# balise_mettrice.net
KiCad netlist of a schematic drawn in EAGLE
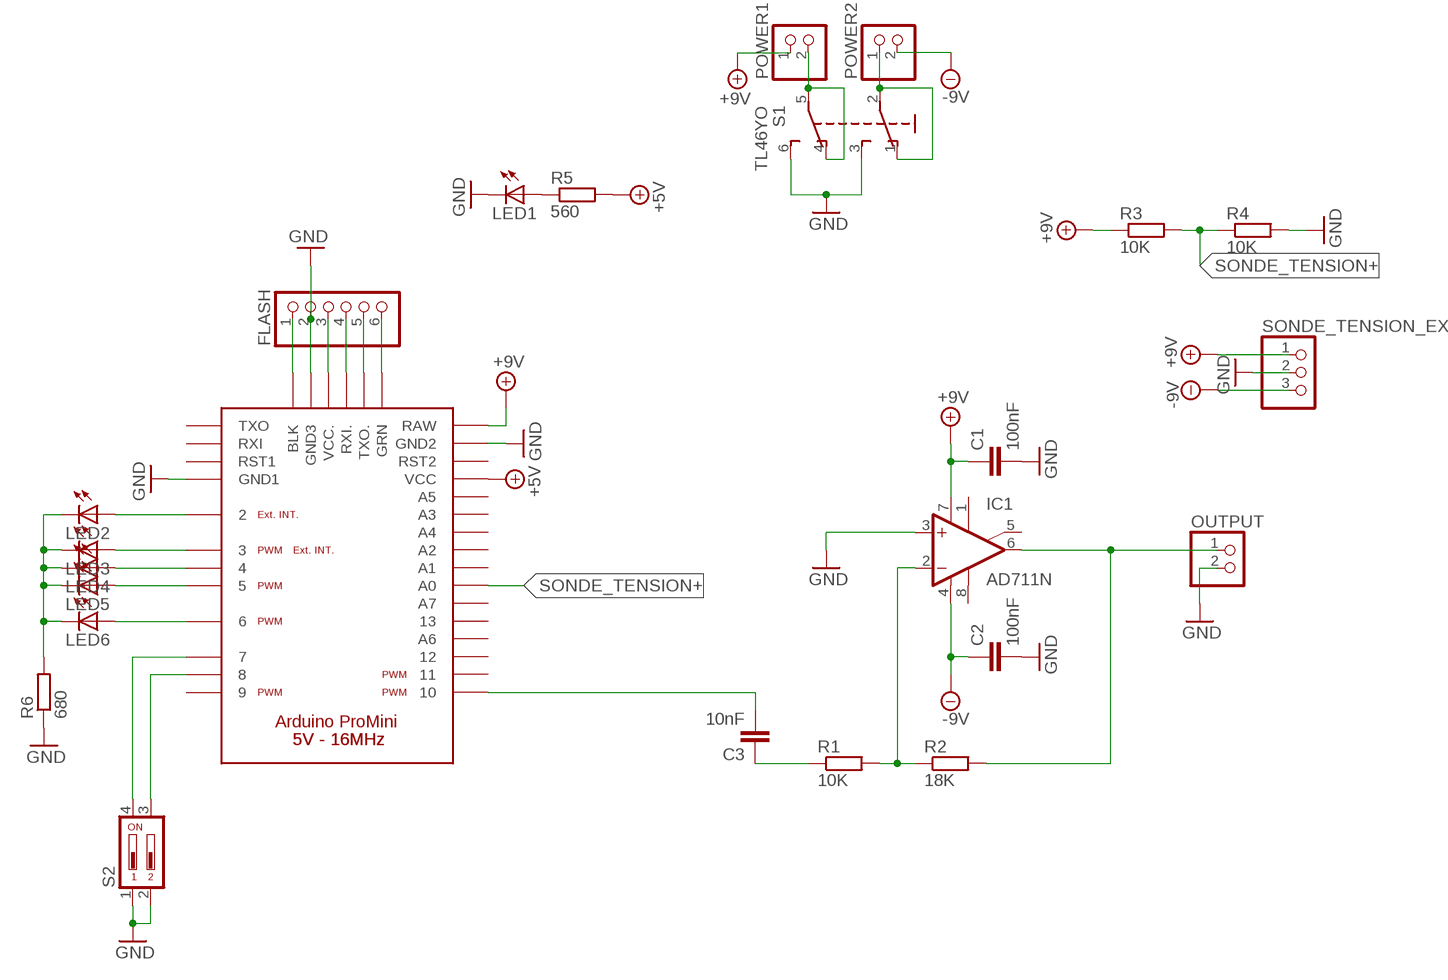
[diagram p0: schematic, sheet 1]

(export (version "E")
  (design (tool "Eeschema 10.0.6"))
  (components
    (comp (ref "C1")
      (value "100nF")
      (footprint "eagle-import:C050-024X044")
      (libsource (lib "eagle-import") (part "C-EU050-024X044"))
    )
    (comp (ref "C2")
      (value "100nF")
      (footprint "eagle-import:C050-024X044")
      (libsource (lib "eagle-import") (part "C-EU050-024X044"))
    )
    (comp (ref "C3")
      (value "10nF")
      (footprint "eagle-import:C050-024X044")
      (libsource (lib "eagle-import") (part "C-EU050-024X044"))
    )
    (comp (ref "FLASH")
      (value "PINHD-1X6/90")
      (footprint "eagle-import:1X06_90")
      (libsource (lib "eagle-import") (part "PINHD-1X6/90"))
    )
    (comp (ref "IC1")
      (value "AD711N")
      (footprint "eagle-import:DIL08")
      (libsource (lib "eagle-import") (part "AD711N"))
    )
    (comp (ref "LED1")
      (value "LEDB155")
      (footprint "eagle-import:Q62902-B155")
      (libsource (lib "eagle-import") (part "LEDB155"))
    )
    (comp (ref "LED2")
      (value "LED3MM")
      (footprint "eagle-import:LED3MM")
      (libsource (lib "eagle-import") (part "LED3MM"))
    )
    (comp (ref "LED3")
      (value "LED3MM")
      (footprint "eagle-import:LED3MM")
      (libsource (lib "eagle-import") (part "LED3MM"))
    )
    (comp (ref "LED4")
      (value "LED3MM")
      (footprint "eagle-import:LED3MM")
      (libsource (lib "eagle-import") (part "LED3MM"))
    )
    (comp (ref "LED5")
      (value "LED3MM")
      (footprint "eagle-import:LED3MM")
      (libsource (lib "eagle-import") (part "LED3MM"))
    )
    (comp (ref "LED6")
      (value "LED3MM")
      (footprint "eagle-import:LED3MM")
      (libsource (lib "eagle-import") (part "LED3MM"))
    )
    (comp (ref "OUTPUT")
      (value "PINHD-1X2")
      (footprint "eagle-import:1X02")
      (libsource (lib "eagle-import") (part "PINHD-1X2"))
    )
    (comp (ref "POWER1")
      (value "PINHD-1X2")
      (footprint "eagle-import:1X02")
      (libsource (lib "eagle-import") (part "PINHD-1X2"))
    )
    (comp (ref "POWER2")
      (value "PINHD-1X2")
      (footprint "eagle-import:1X02")
      (libsource (lib "eagle-import") (part "PINHD-1X2"))
    )
    (comp (ref "R1")
      (value "10K")
      (footprint "eagle-import:0204_7")
      (libsource (lib "eagle-import") (part "R-EU_0204/7"))
    )
    (comp (ref "R2")
      (value "18K")
      (footprint "eagle-import:0204_7")
      (libsource (lib "eagle-import") (part "R-EU_0204/7"))
    )
    (comp (ref "R3")
      (value "10K")
      (footprint "eagle-import:0204_7")
      (libsource (lib "eagle-import") (part "R-EU_0204/7"))
    )
    (comp (ref "R4")
      (value "10K")
      (footprint "eagle-import:0204_7")
      (libsource (lib "eagle-import") (part "R-EU_0204/7"))
    )
    (comp (ref "R5")
      (value "560")
      (footprint "eagle-import:0207_12")
      (libsource (lib "eagle-import") (part "R-EU_0207/12"))
    )
    (comp (ref "R6")
      (value "680")
      (footprint "eagle-import:0204_7")
      (libsource (lib "eagle-import") (part "R-EU_0204/7"))
    )
    (comp (ref "S1")
      (value "TL46YO")
      (footprint "eagle-import:TL4XYO")
      (libsource (lib "eagle-import") (part "TL46YO"))
    )
    (comp (ref "S2")
      (value "DA02")
      (footprint "eagle-import:DA-02")
      (libsource (lib "eagle-import") (part "DA02"))
    )
    (comp (ref "SONDE_TENSION_EXT")
      (value "PINHD-1X3")
      (footprint "eagle-import:1X03")
      (libsource (lib "eagle-import") (part "PINHD-1X3"))
    )
    (comp (ref "U$1")
      (value "ARDUINO_PRO_MINI")
      (footprint "eagle-import:ARDUINO_PRO_MINI")
      (libsource (lib "eagle-import") (part "ARDUINO_PRO_MINI"))
    )
  )
  (nets
    (net (code "1") (name "+5V") (class "Default")
      (node (ref "R5") (pin "2") (pinfunction "2_2") (pintype "passive"))
      (node (ref "U$1") (pin "VCC1") (pinfunction "VCC_VCC1") (pintype "bidirectional"))
    )
    (net (code "2") (name "+9V") (class "Default")
      (node (ref "C1") (pin "1") (pinfunction "1_1") (pintype "passive"))
      (node (ref "IC1") (pin "7") (pinfunction "V+_7") (pintype "power_in"))
      (node (ref "POWER1") (pin "1") (pinfunction "1_1") (pintype "passive"))
      (node (ref "R3") (pin "1") (pinfunction "1_1") (pintype "passive"))
      (node (ref "SONDE_TENSION_EXT") (pin "1") (pinfunction "1_1") (pintype "passive"))
      (node (ref "U$1") (pin "RAW") (pinfunction "RAW_RAW") (pintype "bidirectional"))
    )
    (net (code "3") (name "-9V") (class "Default")
      (node (ref "C2") (pin "1") (pinfunction "1_1") (pintype "passive"))
      (node (ref "IC1") (pin "4") (pinfunction "V-_4") (pintype "power_in"))
      (node (ref "POWER2") (pin "2") (pinfunction "2_2") (pintype "passive"))
      (node (ref "SONDE_TENSION_EXT") (pin "3") (pinfunction "3_3") (pintype "passive"))
    )
    (net (code "4") (name "GND") (class "Default")
      (node (ref "C1") (pin "2") (pinfunction "2_2") (pintype "passive"))
      (node (ref "C2") (pin "2") (pinfunction "2_2") (pintype "passive"))
      (node (ref "FLASH") (pin "2") (pinfunction "2_2") (pintype "passive"))
      (node (ref "IC1") (pin "3") (pinfunction "+IN_3") (pintype "input"))
      (node (ref "LED1") (pin "K") (pinfunction "C_K") (pintype "passive"))
      (node (ref "OUTPUT") (pin "2") (pinfunction "2_2") (pintype "passive"))
      (node (ref "R4") (pin "2") (pinfunction "2_2") (pintype "passive"))
      (node (ref "R6") (pin "1") (pinfunction "1_1") (pintype "passive"))
      (node (ref "S1") (pin "3") (pinfunction "S_3") (pintype "passive"))
      (node (ref "S1") (pin "6") (pinfunction "S1_6") (pintype "passive"))
      (node (ref "S2") (pin "1") (pinfunction "1_1") (pintype "passive"))
      (node (ref "S2") (pin "2") (pinfunction "2_2") (pintype "passive"))
      (node (ref "SONDE_TENSION_EXT") (pin "2") (pinfunction "2_2") (pintype "passive"))
      (node (ref "U$1") (pin "GND1") (pinfunction "GND1_GND1") (pintype "bidirectional"))
      (node (ref "U$1") (pin "GND2") (pinfunction "GND2_GND2") (pintype "bidirectional"))
      (node (ref "U$1") (pin "GND3") (pinfunction "GND3_GND3") (pintype "bidirectional"))
    )
    (net (code "5") (name "Net-(C3-Pad1)") (class "Default")
      (node (ref "C3") (pin "1") (pinfunction "1_1") (pintype "passive"))
      (node (ref "R1") (pin "1") (pinfunction "1_1") (pintype "passive"))
    )
    (net (code "6") (name "Net-(C3-Pad2)") (class "Default")
      (node (ref "C3") (pin "2") (pinfunction "2_2") (pintype "passive"))
      (node (ref "U$1") (pin "10") (pinfunction "10_10") (pintype "bidirectional"))
    )
    (net (code "7") (name "Net-(FLASH-Pad1)") (class "Default")
      (node (ref "FLASH") (pin "1") (pinfunction "1_1") (pintype "passive"))
      (node (ref "U$1") (pin "BLK") (pinfunction "BLK_BLK") (pintype "bidirectional"))
    )
    (net (code "8") (name "Net-(FLASH-Pad6)") (class "Default")
      (node (ref "FLASH") (pin "6") (pinfunction "6_6") (pintype "passive"))
      (node (ref "U$1") (pin "GRN") (pinfunction "GRN_GRN") (pintype "bidirectional"))
    )
    (net (code "9") (name "Net-(IC1--IN)") (class "Default")
      (node (ref "IC1") (pin "2") (pinfunction "-IN_2") (pintype "input"))
      (node (ref "R1") (pin "2") (pinfunction "2_2") (pintype "passive"))
      (node (ref "R2") (pin "1") (pinfunction "1_1") (pintype "passive"))
    )
    (net (code "10") (name "Net-(IC1-OUT)") (class "Default")
      (node (ref "IC1") (pin "6") (pinfunction "OUT_6") (pintype "output"))
      (node (ref "OUTPUT") (pin "1") (pinfunction "1_1") (pintype "passive"))
      (node (ref "R2") (pin "2") (pinfunction "2_2") (pintype "passive"))
    )
    (net (code "11") (name "Net-(LED1-PadA)") (class "Default")
      (node (ref "LED1") (pin "A") (pinfunction "A_A") (pintype "passive"))
      (node (ref "R5") (pin "1") (pinfunction "1_1") (pintype "passive"))
    )
    (net (code "12") (name "Net-(LED2-C)") (class "Default")
      (node (ref "LED2") (pin "K") (pinfunction "C_K") (pintype "passive"))
      (node (ref "LED3") (pin "K") (pinfunction "C_K") (pintype "passive"))
      (node (ref "LED4") (pin "K") (pinfunction "C_K") (pintype "passive"))
      (node (ref "LED5") (pin "K") (pinfunction "C_K") (pintype "passive"))
      (node (ref "LED6") (pin "K") (pinfunction "C_K") (pintype "passive"))
      (node (ref "R6") (pin "2") (pinfunction "2_2") (pintype "passive"))
    )
    (net (code "13") (name "Net-(LED2-PadA)") (class "Default")
      (node (ref "LED2") (pin "A") (pinfunction "A_A") (pintype "passive"))
      (node (ref "U$1") (pin "2") (pinfunction "2_2") (pintype "bidirectional"))
    )
    (net (code "14") (name "Net-(LED3-PadA)") (class "Default")
      (node (ref "LED3") (pin "A") (pinfunction "A_A") (pintype "passive"))
      (node (ref "U$1") (pin "3") (pinfunction "3_3") (pintype "bidirectional"))
    )
    (net (code "15") (name "Net-(LED4-PadA)") (class "Default")
      (node (ref "LED4") (pin "A") (pinfunction "A_A") (pintype "passive"))
      (node (ref "U$1") (pin "4") (pinfunction "4_4") (pintype "bidirectional"))
    )
    (net (code "16") (name "Net-(LED5-PadA)") (class "Default")
      (node (ref "LED5") (pin "A") (pinfunction "A_A") (pintype "passive"))
      (node (ref "U$1") (pin "5") (pinfunction "5_5") (pintype "bidirectional"))
    )
    (net (code "17") (name "Net-(LED6-PadA)") (class "Default")
      (node (ref "LED6") (pin "A") (pinfunction "A_A") (pintype "passive"))
      (node (ref "U$1") (pin "6") (pinfunction "6_6") (pintype "bidirectional"))
    )
    (net (code "18") (name "Net-(S1-O)") (class "Default")
      (node (ref "POWER2") (pin "1") (pinfunction "1_1") (pintype "passive"))
      (node (ref "S1") (pin "1") (pinfunction "O_1") (pintype "passive"))
      (node (ref "S1") (pin "2") (pinfunction "P_2") (pintype "passive"))
    )
    (net (code "19") (name "Net-(S1-O1)") (class "Default")
      (node (ref "POWER1") (pin "2") (pinfunction "2_2") (pintype "passive"))
      (node (ref "S1") (pin "4") (pinfunction "O1_4") (pintype "passive"))
      (node (ref "S1") (pin "5") (pinfunction "P1_5") (pintype "passive"))
    )
    (net (code "20") (name "Net-(S2-Pad3)") (class "Default")
      (node (ref "S2") (pin "3") (pinfunction "3_3") (pintype "passive"))
      (node (ref "U$1") (pin "8") (pinfunction "8_8") (pintype "bidirectional"))
    )
    (net (code "21") (name "Net-(S2-Pad4)") (class "Default")
      (node (ref "S2") (pin "4") (pinfunction "4_4") (pintype "passive"))
      (node (ref "U$1") (pin "7") (pinfunction "7_7") (pintype "bidirectional"))
    )
    (net (code "22") (name "Net-(U$1-RXI.)") (class "Default")
      (node (ref "FLASH") (pin "4") (pinfunction "4_4") (pintype "passive"))
      (node (ref "U$1") (pin "RXI2") (pinfunction "RXI._RXI2") (pintype "bidirectional"))
    )
    (net (code "23") (name "Net-(U$1-TXO.)") (class "Default")
      (node (ref "FLASH") (pin "5") (pinfunction "5_5") (pintype "passive"))
      (node (ref "U$1") (pin "TXO2") (pinfunction "TXO._TXO2") (pintype "bidirectional"))
    )
    (net (code "24") (name "Net-(U$1-VCC.)") (class "Default")
      (node (ref "FLASH") (pin "3") (pinfunction "3_3") (pintype "passive"))
      (node (ref "U$1") (pin "VCC2") (pinfunction "VCC._VCC2") (pintype "bidirectional"))
    )
    (net (code "25") (name "SONDE_TENSION+") (class "Default")
      (node (ref "R3") (pin "2") (pinfunction "2_2") (pintype "passive"))
      (node (ref "R4") (pin "1") (pinfunction "1_1") (pintype "passive"))
      (node (ref "U$1") (pin "A0") (pinfunction "A0_A0") (pintype "bidirectional"))
    )
    (net (code "26") (name "unconnected-(IC1-ON1-Pad1)") (class "Default")
      (node (ref "IC1") (pin "1") (pinfunction "ON1_1") (pintype "passive"))
    )
    (net (code "27") (name "unconnected-(IC1-ON2-Pad5)") (class "Default")
      (node (ref "IC1") (pin "5") (pinfunction "ON2_5") (pintype "passive"))
    )
    (net (code "28") (name "unconnected-(IC1-OPT-Pad8)") (class "Default")
      (node (ref "IC1") (pin "8") (pinfunction "OPT_8") (pintype "passive"))
    )
    (net (code "29") (name "unconnected-(U$1-Pad9)") (class "Default")
      (node (ref "U$1") (pin "9") (pinfunction "9_9") (pintype "bidirectional"))
    )
    (net (code "30") (name "unconnected-(U$1-Pad11)") (class "Default")
      (node (ref "U$1") (pin "11") (pinfunction "11_11") (pintype "bidirectional"))
    )
    (net (code "31") (name "unconnected-(U$1-Pad12)") (class "Default")
      (node (ref "U$1") (pin "12") (pinfunction "12_12") (pintype "bidirectional"))
    )
    (net (code "32") (name "unconnected-(U$1-Pad13)") (class "Default")
      (node (ref "U$1") (pin "13") (pinfunction "13_13") (pintype "bidirectional"))
    )
    (net (code "33") (name "unconnected-(U$1-PadA1)") (class "Default")
      (node (ref "U$1") (pin "A1") (pinfunction "A1_A1") (pintype "bidirectional"))
    )
    (net (code "34") (name "unconnected-(U$1-PadA2)") (class "Default")
      (node (ref "U$1") (pin "A2") (pinfunction "A2_A2") (pintype "bidirectional"))
    )
    (net (code "35") (name "unconnected-(U$1-PadA3)") (class "Default")
      (node (ref "U$1") (pin "A3") (pinfunction "A3_A3") (pintype "bidirectional"))
    )
    (net (code "36") (name "unconnected-(U$1-PadA4)") (class "Default")
      (node (ref "U$1") (pin "A4") (pinfunction "A4_A4") (pintype "bidirectional"))
    )
    (net (code "37") (name "unconnected-(U$1-PadA5)") (class "Default")
      (node (ref "U$1") (pin "A5") (pinfunction "A5_A5") (pintype "bidirectional"))
    )
    (net (code "38") (name "unconnected-(U$1-PadA6)") (class "Default")
      (node (ref "U$1") (pin "A6") (pinfunction "A6_A6") (pintype "bidirectional"))
    )
    (net (code "39") (name "unconnected-(U$1-PadA7)") (class "Default")
      (node (ref "U$1") (pin "A7") (pinfunction "A7_A7") (pintype "bidirectional"))
    )
    (net (code "40") (name "unconnected-(U$1-PadRST1)") (class "Default")
      (node (ref "U$1") (pin "RST1") (pinfunction "RST1_RST1") (pintype "bidirectional"))
    )
    (net (code "41") (name "unconnected-(U$1-PadRST2)") (class "Default")
      (node (ref "U$1") (pin "RST2") (pinfunction "RST2_RST2") (pintype "bidirectional"))
    )
    (net (code "42") (name "unconnected-(U$1-RXI-PadRXI1)") (class "Default")
      (node (ref "U$1") (pin "RXI1") (pinfunction "RXI_RXI1") (pintype "bidirectional"))
    )
    (net (code "43") (name "unconnected-(U$1-TXO-PadTXO1)") (class "Default")
      (node (ref "U$1") (pin "TXO1") (pinfunction "TXO_TXO1") (pintype "bidirectional"))
    )
  )
)
